# P07_PHY_2.net
KiCad netlist of a schematic drawn in Altium Designer
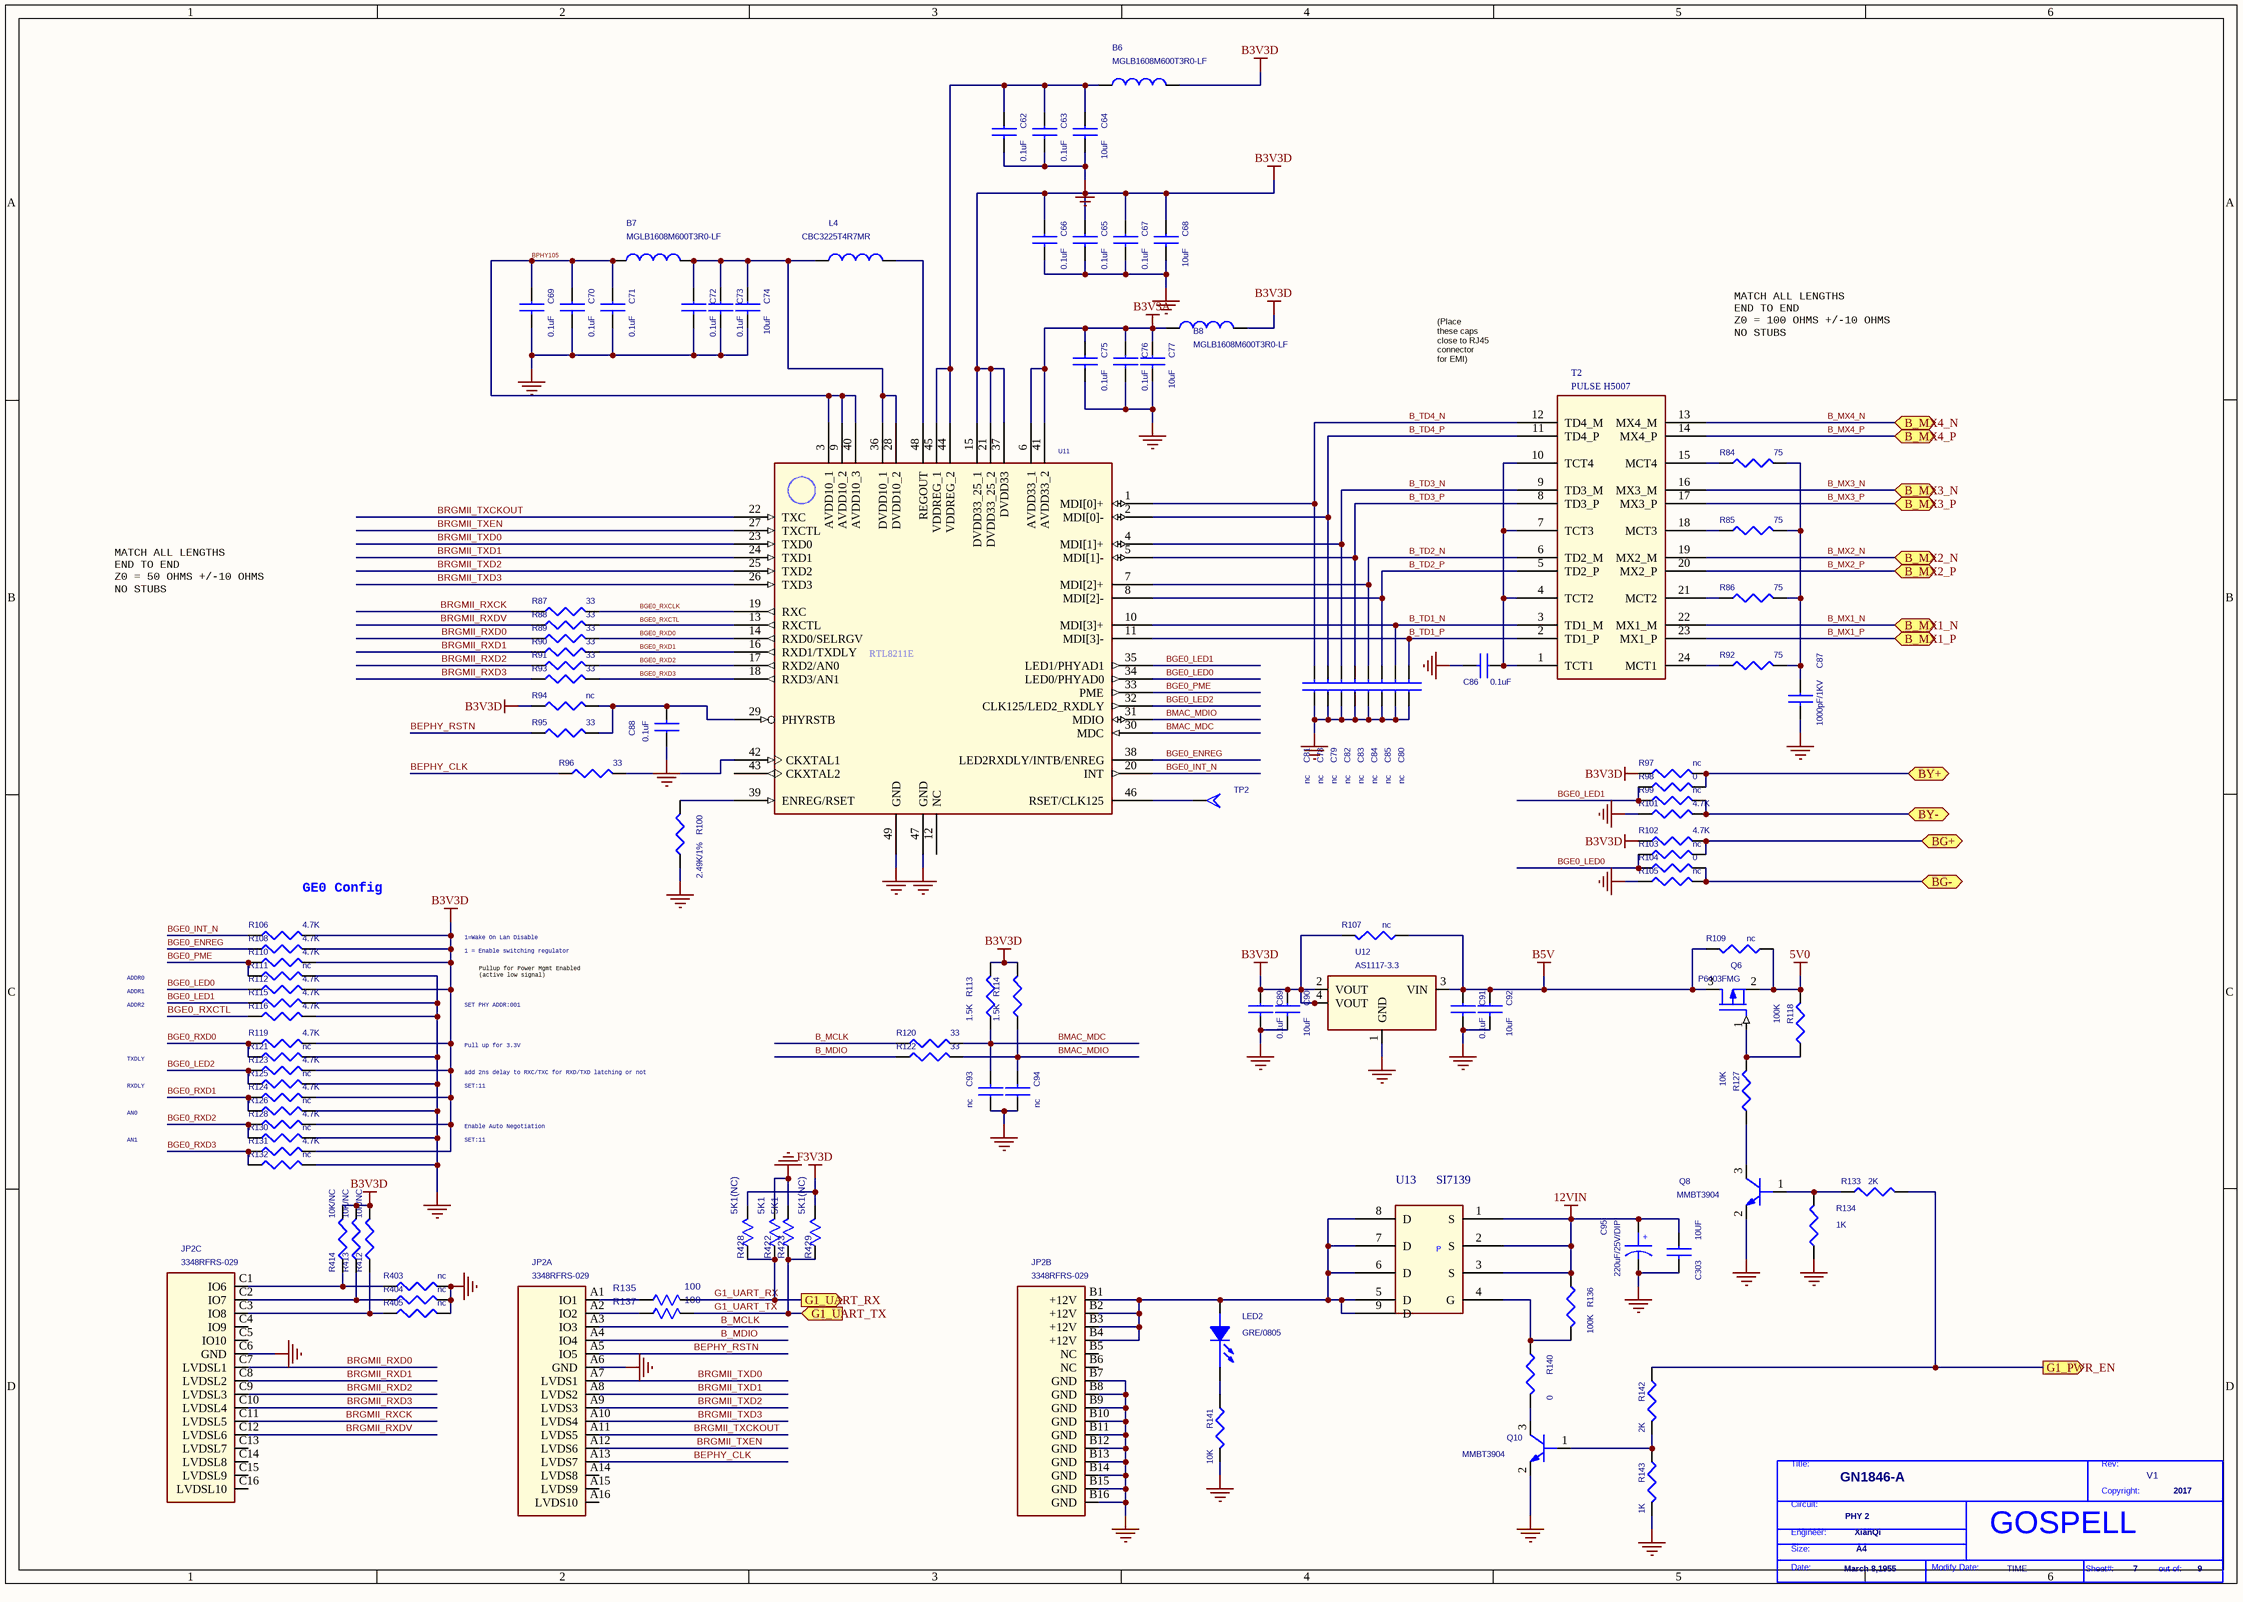
[diagram p0: P07 PHY 2.SchDoc]

(export (version "E")
  (design (tool "Eeschema 10.0.6"))
  (components
    (comp (ref "B6") (value "MGLB1608M600T3R0-LF") (libsource (lib "*") (part "CHOKE TORROID_0")))
    (comp (ref "B7") (value "MGLB1608M600T3R0-LF") (libsource (lib "*") (part "CHOKE TORROID_0")))
    (comp (ref "B8") (value "MGLB1608M600T3R0-LF") (libsource (lib "*") (part "CHOKE TORROID_0")))
    (comp (ref "C62") (value "0.1uF") (libsource (lib "*") (part "CAP NP_Dup1")))
    (comp (ref "C63") (value "0.1uF") (libsource (lib "*") (part "CAP NP_Dup1")))
    (comp (ref "C64") (value "10uF") (libsource (lib "*") (part "CAP NP_Dup1")))
    (comp (ref "C65") (value "0.1uF") (libsource (lib "*") (part "CAP NP_Dup1")))
    (comp (ref "C66") (value "0.1uF") (libsource (lib "*") (part "CAP NP_Dup1")))
    (comp (ref "C67") (value "0.1uF") (libsource (lib "*") (part "CAP NP_Dup1")))
    (comp (ref "C68") (value "10uF") (libsource (lib "*") (part "CAP NP_Dup1")))
    (comp (ref "C69") (value "0.1uF") (libsource (lib "*") (part "CAP NP_Dup1")))
    (comp (ref "C70") (value "0.1uF") (libsource (lib "*") (part "CAP NP_Dup1")))
    (comp (ref "C71") (value "0.1uF") (libsource (lib "*") (part "CAP NP_Dup1")))
    (comp (ref "C72") (value "0.1uF") (libsource (lib "*") (part "CAP NP_Dup1")))
    (comp (ref "C73") (value "0.1uF") (libsource (lib "*") (part "CAP NP_Dup1")))
    (comp (ref "C74") (value "10uF") (libsource (lib "*") (part "CAP NP_Dup1")))
    (comp (ref "C75") (value "0.1uF") (libsource (lib "*") (part "CAP NP_Dup1")))
    (comp (ref "C76") (value "0.1uF") (libsource (lib "*") (part "CAP NP_Dup1")))
    (comp (ref "C77") (value "10uF") (libsource (lib "*") (part "CAP NP_Dup1")))
    (comp (ref "C78") (value "nc") (libsource (lib "*") (part "CAP NP_Dup1")))
    (comp (ref "C79") (value "nc") (libsource (lib "*") (part "CAP NP_Dup1")))
    (comp (ref "C80") (value "nc") (libsource (lib "*") (part "CAP NP_Dup1")))
    (comp (ref "C81") (value "nc") (libsource (lib "*") (part "CAP NP_Dup1")))
    (comp (ref "C82") (value "nc") (libsource (lib "*") (part "CAP NP_Dup1")))
    (comp (ref "C83") (value "nc") (libsource (lib "*") (part "CAP NP_Dup1")))
    (comp (ref "C84") (value "nc") (libsource (lib "*") (part "CAP NP_Dup1")))
    (comp (ref "C85") (value "nc") (libsource (lib "*") (part "CAP NP_Dup1")))
    (comp (ref "C86") (value "0.1uF") (libsource (lib "*") (part "CAP NP_Dup1")))
    (comp (ref "C87") (value "1000pF/1KV") (libsource (lib "*") (part "CAP NP_Dup1")))
    (comp (ref "C88") (value "0.1uF") (libsource (lib "*") (part "CAP NP_Dup1")))
    (comp (ref "C89") (value "0.1uF") (libsource (lib "*") (part "CAP NP_Dup1")))
    (comp (ref "C90") (value "10uF") (libsource (lib "*") (part "CAP NP_Dup1")))
    (comp (ref "C91") (value "0.1uF") (libsource (lib "*") (part "CAP NP_Dup1")))
    (comp (ref "C92") (value "10uF") (libsource (lib "*") (part "CAP NP_Dup1")))
    (comp (ref "C93") (value "nc") (libsource (lib "*") (part "CAP NP_Dup1")))
    (comp (ref "C94") (value "nc") (libsource (lib "*") (part "CAP NP_Dup1")))
    (comp (ref "C95") (value "220uF/25V/DIP") (libsource (lib "*") (part "CAP POL")))
    (comp (ref "C303") (value "10UF") (libsource (lib "*") (part "CAP NP")))
    (comp (ref "JP2")
      (value "3348RFRS-029")
      (footprint "3348RFRS-029")
      (libsource (lib "*") (part "3348RFRS-029"))
    )
    (comp (ref "L4") (value "CBC3225T4R7MR") (libsource (lib "*") (part "CHOKE TORROID_0")))
    (comp (ref "LED2") (value "GRE/0805") (libsource (lib "*") (part "LED_0")))
    (comp (ref "Q6") (value "P6403FMG") (libsource (lib "*") (part "MOSFET P_0")))
    (comp (ref "Q8") (value "MMBT3904") (footprint "SOT23") (libsource (lib "*") (part "2N3904")))
    (comp (ref "Q10") (value "MMBT3904") (footprint "SOT23") (libsource (lib "*") (part "2N3904")))
    (comp (ref "R84") (value "75") (libsource (lib "*") (part "R_Dup1")))
    (comp (ref "R85") (value "75") (libsource (lib "*") (part "R_Dup1")))
    (comp (ref "R86") (value "75") (libsource (lib "*") (part "R_Dup1")))
    (comp (ref "R87") (value "33") (libsource (lib "*") (part "R_Dup1")))
    (comp (ref "R88") (value "33") (libsource (lib "*") (part "R_Dup1")))
    (comp (ref "R89") (value "33") (libsource (lib "*") (part "R_Dup1")))
    (comp (ref "R90") (value "33") (libsource (lib "*") (part "R_Dup1")))
    (comp (ref "R91") (value "33") (libsource (lib "*") (part "R_Dup1")))
    (comp (ref "R92") (value "75") (libsource (lib "*") (part "R_Dup1")))
    (comp (ref "R93") (value "33") (libsource (lib "*") (part "R_Dup1")))
    (comp (ref "R94") (value "nc") (libsource (lib "*") (part "R_Dup1")))
    (comp (ref "R95") (value "33") (libsource (lib "*") (part "R_Dup1")))
    (comp (ref "R96") (value "33") (libsource (lib "*") (part "R_Dup1")))
    (comp (ref "R97") (value "nc") (libsource (lib "*") (part "R_Dup1")))
    (comp (ref "R98") (value "0") (libsource (lib "*") (part "R_Dup1")))
    (comp (ref "R99") (value "nc") (libsource (lib "*") (part "R_Dup1")))
    (comp (ref "R100") (value "2.49K/1%") (libsource (lib "*") (part "R_Dup1")))
    (comp (ref "R101") (value "4.7K") (libsource (lib "*") (part "R_Dup1")))
    (comp (ref "R102") (value "4.7K") (libsource (lib "*") (part "R_Dup1")))
    (comp (ref "R103") (value "nc") (libsource (lib "*") (part "R_Dup1")))
    (comp (ref "R104") (value "0") (libsource (lib "*") (part "R_Dup1")))
    (comp (ref "R105") (value "nc") (libsource (lib "*") (part "R_Dup1")))
    (comp (ref "R106") (value "4.7K") (libsource (lib "*") (part "R_Dup1")))
    (comp (ref "R107") (value "nc") (libsource (lib "*") (part "R")))
    (comp (ref "R108") (value "4.7K") (libsource (lib "*") (part "R_Dup1")))
    (comp (ref "R109") (value "nc") (libsource (lib "*") (part "R")))
    (comp (ref "R110") (value "4.7K") (libsource (lib "*") (part "R_Dup1")))
    (comp (ref "R111") (value "nc") (libsource (lib "*") (part "R_Dup1")))
    (comp (ref "R112") (value "4.7K") (libsource (lib "*") (part "R_Dup1")))
    (comp (ref "R113") (value "1.5K") (libsource (lib "*") (part "R_Dup1")))
    (comp (ref "R114") (value "1.5K") (libsource (lib "*") (part "R_Dup1")))
    (comp (ref "R115") (value "4.7K") (libsource (lib "*") (part "R_Dup1")))
    (comp (ref "R116") (value "4.7K") (libsource (lib "*") (part "R_Dup1")))
    (comp (ref "R118") (value "100K") (libsource (lib "*") (part "R")))
    (comp (ref "R119") (value "4.7K") (libsource (lib "*") (part "R_Dup1")))
    (comp (ref "R120") (value "33") (libsource (lib "*") (part "R_Dup1")))
    (comp (ref "R121") (value "nc") (libsource (lib "*") (part "R_Dup1")))
    (comp (ref "R122") (value "33") (libsource (lib "*") (part "R_Dup1")))
    (comp (ref "R123") (value "4.7K") (libsource (lib "*") (part "R_Dup1")))
    (comp (ref "R124") (value "4.7K") (libsource (lib "*") (part "R_Dup1")))
    (comp (ref "R125") (value "nc") (libsource (lib "*") (part "R_Dup1")))
    (comp (ref "R126") (value "nc") (libsource (lib "*") (part "R_Dup1")))
    (comp (ref "R127") (value "10K") (libsource (lib "*") (part "R")))
    (comp (ref "R128") (value "4.7K") (libsource (lib "*") (part "R_Dup1")))
    (comp (ref "R130") (value "nc") (libsource (lib "*") (part "R_Dup1")))
    (comp (ref "R131") (value "4.7K") (libsource (lib "*") (part "R_Dup1")))
    (comp (ref "R132") (value "nc") (libsource (lib "*") (part "R_Dup1")))
    (comp (ref "R133") (value "2K") (libsource (lib "*") (part "R")))
    (comp (ref "R134") (value "1K") (libsource (lib "*") (part "R")))
    (comp (ref "R135") (value "100") (libsource (lib "*") (part "R_1")))
    (comp (ref "R136") (value "100K") (libsource (lib "*") (part "R_Dup1")))
    (comp (ref "R137") (value "100") (libsource (lib "*") (part "R_1")))
    (comp (ref "R140") (value "0") (libsource (lib "*") (part "R_Dup1")))
    (comp (ref "R141") (value "10K") (libsource (lib "*") (part "R_Dup1")))
    (comp (ref "R142") (value "2K") (libsource (lib "*") (part "R_Dup1")))
    (comp (ref "R143") (value "1K") (libsource (lib "*") (part "R_Dup1")))
    (comp (ref "R403") (value "nc") (libsource (lib "*") (part "R_Dup1")))
    (comp (ref "R404") (value "nc") (libsource (lib "*") (part "R_Dup1")))
    (comp (ref "R405") (value "nc") (libsource (lib "*") (part "R_Dup1")))
    (comp (ref "R412") (value "10K/NC") (libsource (lib "*") (part "R_Dup1")))
    (comp (ref "R413") (value "10K/NC") (libsource (lib "*") (part "R_Dup1")))
    (comp (ref "R414") (value "10K/NC") (libsource (lib "*") (part "R_Dup1")))
    (comp (ref "R422") (value "5K1") (libsource (lib "*") (part "R_1")))
    (comp (ref "R423") (value "5K1") (libsource (lib "*") (part "R_1")))
    (comp (ref "R428") (value "5K1(NC)") (libsource (lib "*") (part "R_1")))
    (comp (ref "R429") (value "5K1(NC)") (libsource (lib "*") (part "R_1")))
    (comp (ref "T2") (value "PULSE H5007") (footprint "H5007-H") (libsource (lib "*") (part "PULSE H5007_0")))
    (comp (ref "TP2") (value "T POINT A") (libsource (lib "*") (part "T POINT A")))
    (comp (ref "U11")
      (value "RTL8211D")
      (footprint "QFN-48P-RTL8211")
      (libsource (lib "*") (part "RTL8211D_1"))
    )
    (comp (ref "U12") (value "AS1117-3.3") (footprint "SOT223") (libsource (lib "*") (part "AS1117-X_1")))
    (comp (ref "U13")
      (value "SI7139")
      (footprint "PowerPAKSO8")
      (libsource (lib "GN-1846-A-V1_Library") (part "SI7139"))
    )
  )
  (nets
    (net (code "1") (name "/BEPHY_CLK") (class "Default")
      (node (ref "JP2") (pin "A13") (pinfunction "LVDS7_A13") (pintype "passive"))
      (node (ref "R96") (pin "1") (pinfunction "1_1") (pintype "passive"))
    )
    (net (code "2") (name "/BEPHY_RSTN") (class "Default")
      (node (ref "JP2") (pin "A5") (pinfunction "IO5_A5") (pintype "passive"))
      (node (ref "R95") (pin "1") (pinfunction "1_1") (pintype "passive"))
    )
    (net (code "3") (name "/BG+") (class "Default")
      (node (ref "R102") (pin "2") (pinfunction "2_2") (pintype "passive"))
      (node (ref "R103") (pin "2") (pinfunction "2_2") (pintype "passive"))
    )
    (net (code "4") (name "/BG-") (class "Default")
      (node (ref "R104") (pin "2") (pinfunction "2_2") (pintype "passive"))
      (node (ref "R105") (pin "2") (pinfunction "2_2") (pintype "passive"))
    )
    (net (code "5") (name "/BGE0_ENREG") (class "Default")
      (node (ref "R108") (pin "1") (pinfunction "1_1") (pintype "passive"))
      (node (ref "U11") (pin "38") (pinfunction "LED2RXDLY/INTB/ENREG_38") (pintype "passive"))
    )
    (net (code "6") (name "/BGE0_INT_N") (class "Default")
      (node (ref "R106") (pin "1") (pinfunction "1_1") (pintype "passive"))
      (node (ref "U11") (pin "20") (pinfunction "INT_20") (pintype "output"))
    )
    (net (code "7") (name "/BGE0_LED0") (class "Default")
      (node (ref "R103") (pin "1") (pinfunction "1_1") (pintype "passive"))
      (node (ref "R104") (pin "1") (pinfunction "1_1") (pintype "passive"))
      (node (ref "R112") (pin "1") (pinfunction "1_1") (pintype "passive"))
      (node (ref "U11") (pin "34") (pinfunction "LED0/PHYAD0_34") (pintype "output"))
    )
    (net (code "8") (name "/BGE0_LED1") (class "Default")
      (node (ref "R115") (pin "1") (pinfunction "1_1") (pintype "passive"))
      (node (ref "R98") (pin "1") (pinfunction "1_1") (pintype "passive"))
      (node (ref "R99") (pin "1") (pinfunction "1_1") (pintype "passive"))
      (node (ref "U11") (pin "35") (pinfunction "LED1/PHYAD1_35") (pintype "output"))
    )
    (net (code "9") (name "/BGE0_LED2") (class "Default")
      (node (ref "R123") (pin "1") (pinfunction "1_1") (pintype "passive"))
      (node (ref "R125") (pin "1") (pinfunction "1_1") (pintype "passive"))
      (node (ref "U11") (pin "32") (pinfunction "CLK125/LED2_RXDLY_32") (pintype "output"))
    )
    (net (code "10") (name "/BGE0_PME") (class "Default")
      (node (ref "R110") (pin "1") (pinfunction "1_1") (pintype "passive"))
      (node (ref "R111") (pin "1") (pinfunction "1_1") (pintype "passive"))
      (node (ref "U11") (pin "33") (pinfunction "PME_33") (pintype "output"))
    )
    (net (code "11") (name "/BGE0_RXCLK") (class "Default")
      (node (ref "R87") (pin "2") (pinfunction "2_2") (pintype "passive"))
      (node (ref "U11") (pin "19") (pinfunction "RXC_19") (pintype "output"))
    )
    (net (code "12") (name "/BGE0_RXCTL") (class "Default")
      (node (ref "R116") (pin "1") (pinfunction "1_1") (pintype "passive"))
      (node (ref "R88") (pin "2") (pinfunction "2_2") (pintype "passive"))
      (node (ref "U11") (pin "13") (pinfunction "RXCTL_13") (pintype "output"))
    )
    (net (code "13") (name "/BGE0_RXD0") (class "Default")
      (node (ref "R119") (pin "1") (pinfunction "1_1") (pintype "passive"))
      (node (ref "R121") (pin "1") (pinfunction "1_1") (pintype "passive"))
      (node (ref "R89") (pin "2") (pinfunction "2_2") (pintype "passive"))
      (node (ref "U11") (pin "14") (pinfunction "RXD0/SELRGV_14") (pintype "output"))
    )
    (net (code "14") (name "/BGE0_RXD1") (class "Default")
      (node (ref "R124") (pin "1") (pinfunction "1_1") (pintype "passive"))
      (node (ref "R126") (pin "1") (pinfunction "1_1") (pintype "passive"))
      (node (ref "R90") (pin "2") (pinfunction "2_2") (pintype "passive"))
      (node (ref "U11") (pin "16") (pinfunction "RXD1/TXDLY_16") (pintype "output"))
    )
    (net (code "15") (name "/BGE0_RXD2") (class "Default")
      (node (ref "R128") (pin "1") (pinfunction "1_1") (pintype "passive"))
      (node (ref "R130") (pin "1") (pinfunction "1_1") (pintype "passive"))
      (node (ref "R91") (pin "2") (pinfunction "2_2") (pintype "passive"))
      (node (ref "U11") (pin "17") (pinfunction "RXD2/AN0_17") (pintype "output"))
    )
    (net (code "16") (name "/BGE0_RXD3") (class "Default")
      (node (ref "R131") (pin "1") (pinfunction "1_1") (pintype "passive"))
      (node (ref "R132") (pin "1") (pinfunction "1_1") (pintype "passive"))
      (node (ref "R93") (pin "2") (pinfunction "2_2") (pintype "passive"))
      (node (ref "U11") (pin "18") (pinfunction "RXD3/AN1_18") (pintype "output"))
    )
    (net (code "17") (name "/BMAC_MDC") (class "Default")
      (node (ref "C93") (pin "2") (pinfunction "2_2") (pintype "passive"))
      (node (ref "R113") (pin "1") (pinfunction "1_1") (pintype "passive"))
      (node (ref "R120") (pin "2") (pinfunction "2_2") (pintype "passive"))
      (node (ref "U11") (pin "30") (pinfunction "MDC_30") (pintype "input"))
    )
    (net (code "18") (name "/BMAC_MDIO") (class "Default")
      (node (ref "C94") (pin "2") (pinfunction "2_2") (pintype "passive"))
      (node (ref "R114") (pin "1") (pinfunction "1_1") (pintype "passive"))
      (node (ref "R122") (pin "2") (pinfunction "2_2") (pintype "passive"))
      (node (ref "U11") (pin "31") (pinfunction "MDIO_31") (pintype "bidirectional"))
    )
    (net (code "19") (name "/BPHY105") (class "Default")
      (node (ref "B7") (pin "1") (pinfunction "1_1") (pintype "passive"))
      (node (ref "C69") (pin "1") (pinfunction "1_1") (pintype "passive"))
      (node (ref "C70") (pin "1") (pinfunction "1_1") (pintype "passive"))
      (node (ref "C71") (pin "1") (pinfunction "1_1") (pintype "passive"))
      (node (ref "U11") (pin "3") (pinfunction "AVDD10_1_3") (pintype "power_in"))
      (node (ref "U11") (pin "40") (pinfunction "AVDD10_3_40") (pintype "power_in"))
      (node (ref "U11") (pin "9") (pinfunction "AVDD10_2_9") (pintype "power_in"))
    )
    (net (code "20") (name "/BRGMII_RXCK") (class "Default")
      (node (ref "JP2") (pin "C11") (pinfunction "LVDSL5_C11") (pintype "passive"))
      (node (ref "R87") (pin "1") (pinfunction "1_1") (pintype "passive"))
    )
    (net (code "21") (name "/BRGMII_RXD0") (class "Default")
      (node (ref "JP2") (pin "C7") (pinfunction "LVDSL1_C7") (pintype "passive"))
      (node (ref "R89") (pin "1") (pinfunction "1_1") (pintype "passive"))
    )
    (net (code "22") (name "/BRGMII_RXD1") (class "Default")
      (node (ref "JP2") (pin "C8") (pinfunction "LVDSL2_C8") (pintype "passive"))
      (node (ref "R90") (pin "1") (pinfunction "1_1") (pintype "passive"))
    )
    (net (code "23") (name "/BRGMII_RXD2") (class "Default")
      (node (ref "JP2") (pin "C9") (pinfunction "LVDSL3_C9") (pintype "passive"))
      (node (ref "R91") (pin "1") (pinfunction "1_1") (pintype "passive"))
    )
    (net (code "24") (name "/BRGMII_RXD3") (class "Default")
      (node (ref "JP2") (pin "C10") (pinfunction "LVDSL4_C10") (pintype "passive"))
      (node (ref "R93") (pin "1") (pinfunction "1_1") (pintype "passive"))
    )
    (net (code "25") (name "/BRGMII_RXDV") (class "Default")
      (node (ref "JP2") (pin "C12") (pinfunction "LVDSL6_C12") (pintype "passive"))
      (node (ref "R88") (pin "1") (pinfunction "1_1") (pintype "passive"))
    )
    (net (code "26") (name "/BRGMII_TXCKOUT") (class "Default")
      (node (ref "JP2") (pin "A11") (pinfunction "LVDS5_A11") (pintype "passive"))
      (node (ref "U11") (pin "22") (pinfunction "TXC_22") (pintype "input"))
    )
    (net (code "27") (name "/BRGMII_TXD0") (class "Default")
      (node (ref "JP2") (pin "A7") (pinfunction "LVDS1_A7") (pintype "passive"))
      (node (ref "U11") (pin "23") (pinfunction "TXD0_23") (pintype "input"))
    )
    (net (code "28") (name "/BRGMII_TXD1") (class "Default")
      (node (ref "JP2") (pin "A8") (pinfunction "LVDS2_A8") (pintype "passive"))
      (node (ref "U11") (pin "24") (pinfunction "TXD1_24") (pintype "input"))
    )
    (net (code "29") (name "/BRGMII_TXD2") (class "Default")
      (node (ref "JP2") (pin "A9") (pinfunction "LVDS3_A9") (pintype "passive"))
      (node (ref "U11") (pin "25") (pinfunction "TXD2_25") (pintype "input"))
    )
    (net (code "30") (name "/BRGMII_TXD3") (class "Default")
      (node (ref "JP2") (pin "A10") (pinfunction "LVDS4_A10") (pintype "passive"))
      (node (ref "U11") (pin "26") (pinfunction "TXD3_26") (pintype "input"))
    )
    (net (code "31") (name "/BRGMII_TXEN") (class "Default")
      (node (ref "JP2") (pin "A12") (pinfunction "LVDS6_A12") (pintype "passive"))
      (node (ref "U11") (pin "27") (pinfunction "TXCTL_27") (pintype "input"))
    )
    (net (code "32") (name "/BY+") (class "Default")
      (node (ref "R97") (pin "2") (pinfunction "2_2") (pintype "passive"))
      (node (ref "R98") (pin "2") (pinfunction "2_2") (pintype "passive"))
    )
    (net (code "33") (name "/BY-") (class "Default")
      (node (ref "R101") (pin "2") (pinfunction "2_2") (pintype "passive"))
      (node (ref "R99") (pin "2") (pinfunction "2_2") (pintype "passive"))
    )
    (net (code "34") (name "/B_MCLK") (class "Default")
      (node (ref "JP2") (pin "A3") (pinfunction "IO3_A3") (pintype "passive"))
      (node (ref "R120") (pin "1") (pinfunction "1_1") (pintype "passive"))
    )
    (net (code "35") (name "/B_MDIO") (class "Default")
      (node (ref "JP2") (pin "A4") (pinfunction "IO4_A4") (pintype "passive"))
      (node (ref "R122") (pin "1") (pinfunction "1_1") (pintype "passive"))
    )
    (net (code "36") (name "/B_MX1_N") (class "Default")
      (node (ref "T2") (pin "22") (pinfunction "MX1_M_22") (pintype "passive"))
    )
    (net (code "37") (name "/B_MX1_P") (class "Default")
      (node (ref "T2") (pin "23") (pinfunction "MX1_P_23") (pintype "passive"))
    )
    (net (code "38") (name "/B_MX2_N") (class "Default")
      (node (ref "T2") (pin "19") (pinfunction "MX2_M_19") (pintype "passive"))
    )
    (net (code "39") (name "/B_MX2_P") (class "Default")
      (node (ref "T2") (pin "20") (pinfunction "MX2_P_20") (pintype "passive"))
    )
    (net (code "40") (name "/B_MX3_N") (class "Default")
      (node (ref "T2") (pin "16") (pinfunction "MX3_M_16") (pintype "passive"))
    )
    (net (code "41") (name "/B_MX3_P") (class "Default")
      (node (ref "T2") (pin "17") (pinfunction "MX3_P_17") (pintype "passive"))
    )
    (net (code "42") (name "/B_MX4_N") (class "Default")
      (node (ref "T2") (pin "13") (pinfunction "MX4_M_13") (pintype "passive"))
    )
    (net (code "43") (name "/B_MX4_P") (class "Default")
      (node (ref "T2") (pin "14") (pinfunction "MX4_P_14") (pintype "passive"))
    )
    (net (code "44") (name "/B_TD1_N") (class "Default")
      (node (ref "C85") (pin "2") (pinfunction "2_2") (pintype "passive"))
      (node (ref "T2") (pin "3") (pinfunction "TD1_M_3") (pintype "passive"))
      (node (ref "U11") (pin "10") (pinfunction "MDI[3]+_10") (pintype "passive"))
    )
    (net (code "45") (name "/B_TD1_P") (class "Default")
      (node (ref "C80") (pin "2") (pinfunction "2_2") (pintype "passive"))
      (node (ref "T2") (pin "2") (pinfunction "TD1_P_2") (pintype "passive"))
      (node (ref "U11") (pin "11") (pinfunction "MDI[3]-_11") (pintype "passive"))
    )
    (net (code "46") (name "/B_TD2_N") (class "Default")
      (node (ref "C83") (pin "2") (pinfunction "2_2") (pintype "passive"))
      (node (ref "T2") (pin "6") (pinfunction "TD2_M_6") (pintype "passive"))
      (node (ref "U11") (pin "7") (pinfunction "MDI[2]+_7") (pintype "passive"))
    )
    (net (code "47") (name "/B_TD2_P") (class "Default")
      (node (ref "C84") (pin "2") (pinfunction "2_2") (pintype "passive"))
      (node (ref "T2") (pin "5") (pinfunction "TD2_P_5") (pintype "passive"))
      (node (ref "U11") (pin "8") (pinfunction "MDI[2]-_8") (pintype "passive"))
    )
    (net (code "48") (name "/B_TD3_N") (class "Default")
      (node (ref "C79") (pin "2") (pinfunction "2_2") (pintype "passive"))
      (node (ref "T2") (pin "9") (pinfunction "TD3_M_9") (pintype "passive"))
      (node (ref "U11") (pin "4") (pinfunction "MDI[1]+_4") (pintype "bidirectional"))
    )
    (net (code "49") (name "/B_TD3_P") (class "Default")
      (node (ref "C82") (pin "2") (pinfunction "2_2") (pintype "passive"))
      (node (ref "T2") (pin "8") (pinfunction "TD3_P_8") (pintype "passive"))
      (node (ref "U11") (pin "5") (pinfunction "MDI[1]-_5") (pintype "bidirectional"))
    )
    (net (code "50") (name "/B_TD4_N") (class "Default")
      (node (ref "C81") (pin "2") (pinfunction "2_2") (pintype "passive"))
      (node (ref "T2") (pin "12") (pinfunction "TD4_M_12") (pintype "passive"))
      (node (ref "U11") (pin "1") (pinfunction "MDI[0]+_1") (pintype "bidirectional"))
    )
    (net (code "51") (name "/B_TD4_P") (class "Default")
      (node (ref "C78") (pin "2") (pinfunction "2_2") (pintype "passive"))
      (node (ref "T2") (pin "11") (pinfunction "TD4_P_11") (pintype "passive"))
      (node (ref "U11") (pin "2") (pinfunction "MDI[0]-_2") (pintype "bidirectional"))
    )
    (net (code "52") (name "/G1_PWR_EN") (class "Default")
      (node (ref "R133") (pin "2") (pinfunction "2_2") (pintype "passive"))
      (node (ref "R142") (pin "2") (pinfunction "2_2") (pintype "passive"))
    )
    (net (code "53") (name "/G1_UART_RX") (class "Default")
      (node (ref "R135") (pin "2") (pinfunction "B_2") (pintype "passive"))
      (node (ref "R422") (pin "1") (pinfunction "A_1") (pintype "passive"))
      (node (ref "R428") (pin "1") (pinfunction "A_1") (pintype "passive"))
    )
    (net (code "54") (name "/G1_UART_TX") (class "Default")
      (node (ref "R137") (pin "2") (pinfunction "B_2") (pintype "passive"))
      (node (ref "R423") (pin "1") (pinfunction "A_1") (pintype "passive"))
      (node (ref "R429") (pin "1") (pinfunction "A_1") (pintype "passive"))
    )
    (net (code "55") (name "5V0") (class "Default")
      (node (ref "Q6") (pin "2") (pinfunction "SOURCE_2") (pintype "passive"))
      (node (ref "R109") (pin "2") (pinfunction "2_2") (pintype "passive"))
      (node (ref "R118") (pin "1") (pinfunction "1_1") (pintype "passive"))
    )
    (net (code "56") (name "12VIN") (class "Default")
      (node (ref "C303") (pin "1") (pinfunction "1_1") (pintype "passive"))
      (node (ref "C95") (pin "1") (pinfunction "1_1") (pintype "passive"))
      (node (ref "R136") (pin "2") (pinfunction "2_2") (pintype "passive"))
      (node (ref "U13") (pin "1") (pinfunction "S_1") (pintype "passive"))
      (node (ref "U13") (pin "2") (pinfunction "S_2") (pintype "passive"))
      (node (ref "U13") (pin "3") (pinfunction "S_3") (pintype "passive"))
    )
    (net (code "57") (name "B3V3A") (class "Default")
      (node (ref "B8") (pin "1") (pinfunction "1_1") (pintype "passive"))
      (node (ref "C75") (pin "1") (pinfunction "1_1") (pintype "passive"))
      (node (ref "C76") (pin "1") (pinfunction "1_1") (pintype "passive"))
      (node (ref "C77") (pin "1") (pinfunction "1_1") (pintype "passive"))
      (node (ref "U11") (pin "41") (pinfunction "AVDD33_2_41") (pintype "power_in"))
      (node (ref "U11") (pin "6") (pinfunction "AVDD33_1_6") (pintype "power_in"))
    )
    (net (code "58") (name "B3V3D") (class "Default")
      (node (ref "B6") (pin "2") (pinfunction "2_2") (pintype "passive"))
      (node (ref "B8") (pin "2") (pinfunction "2_2") (pintype "passive"))
      (node (ref "C65") (pin "1") (pinfunction "1_1") (pintype "passive"))
      (node (ref "C66") (pin "1") (pinfunction "1_1") (pintype "passive"))
      (node (ref "C67") (pin "1") (pinfunction "1_1") (pintype "passive"))
      (node (ref "C68") (pin "1") (pinfunction "1_1") (pintype "passive"))
      (node (ref "C89") (pin "1") (pinfunction "1_1") (pintype "passive"))
      (node (ref "C90") (pin "1") (pinfunction "1_1") (pintype "passive"))
      (node (ref "R102") (pin "1") (pinfunction "1_1") (pintype "passive"))
      (node (ref "R106") (pin "2") (pinfunction "2_2") (pintype "passive"))
      (node (ref "R107") (pin "1") (pinfunction "1_1") (pintype "passive"))
      (node (ref "R108") (pin "2") (pinfunction "2_2") (pintype "passive"))
      (node (ref "R110") (pin "2") (pinfunction "2_2") (pintype "passive"))
      (node (ref "R112") (pin "2") (pinfunction "2_2") (pintype "passive"))
      (node (ref "R113") (pin "2") (pinfunction "2_2") (pintype "passive"))
      (node (ref "R114") (pin "2") (pinfunction "2_2") (pintype "passive"))
      (node (ref "R119") (pin "2") (pinfunction "2_2") (pintype "passive"))
      (node (ref "R123") (pin "2") (pinfunction "2_2") (pintype "passive"))
      (node (ref "R124") (pin "2") (pinfunction "2_2") (pintype "passive"))
      (node (ref "R128") (pin "2") (pinfunction "2_2") (pintype "passive"))
      (node (ref "R131") (pin "2") (pinfunction "2_2") (pintype "passive"))
      (node (ref "R412") (pin "2") (pinfunction "2_2") (pintype "passive"))
      (node (ref "R413") (pin "2") (pinfunction "2_2") (pintype "passive"))
      (node (ref "R414") (pin "2") (pinfunction "2_2") (pintype "passive"))
      (node (ref "R94") (pin "1") (pinfunction "1_1") (pintype "passive"))
      (node (ref "R97") (pin "1") (pinfunction "1_1") (pintype "passive"))
      (node (ref "U11") (pin "15") (pinfunction "DVDD33_25_1_15") (pintype "power_in"))
      (node (ref "U11") (pin "21") (pinfunction "DVDD33_25_2_21") (pintype "power_in"))
      (node (ref "U11") (pin "37") (pinfunction "DVDD33_37") (pintype "power_in"))
      (node (ref "U12") (pin "2") (pinfunction "VOUT_2") (pintype "passive"))
      (node (ref "U12") (pin "4") (pinfunction "VOUT_4") (pintype "passive"))
    )
    (net (code "59") (name "B5V") (class "Default")
      (node (ref "C91") (pin "1") (pinfunction "1_1") (pintype "passive"))
      (node (ref "C92") (pin "1") (pinfunction "1_1") (pintype "passive"))
      (node (ref "Q6") (pin "3") (pinfunction "DRAIN_3") (pintype "passive"))
      (node (ref "R107") (pin "2") (pinfunction "2_2") (pintype "passive"))
      (node (ref "R109") (pin "1") (pinfunction "1_1") (pintype "passive"))
      (node (ref "U12") (pin "3") (pinfunction "VIN_3") (pintype "passive"))
    )
    (net (code "60") (name "F3V3D") (class "Default")
      (node (ref "R428") (pin "2") (pinfunction "B_2") (pintype "passive"))
      (node (ref "R429") (pin "2") (pinfunction "B_2") (pintype "passive"))
    )
    (net (code "61") (name "GND") (class "Default")
      (node (ref "C303") (pin "2") (pinfunction "2_2") (pintype "passive"))
      (node (ref "C62") (pin "2") (pinfunction "2_2") (pintype "passive"))
      (node (ref "C63") (pin "2") (pinfunction "2_2") (pintype "passive"))
      (node (ref "C64") (pin "2") (pinfunction "2_2") (pintype "passive"))
      (node (ref "C65") (pin "2") (pinfunction "2_2") (pintype "passive"))
      (node (ref "C66") (pin "2") (pinfunction "2_2") (pintype "passive"))
      (node (ref "C67") (pin "2") (pinfunction "2_2") (pintype "passive"))
      (node (ref "C68") (pin "2") (pinfunction "2_2") (pintype "passive"))
      (node (ref "C69") (pin "2") (pinfunction "2_2") (pintype "passive"))
      (node (ref "C70") (pin "2") (pinfunction "2_2") (pintype "passive"))
      (node (ref "C71") (pin "2") (pinfunction "2_2") (pintype "passive"))
      (node (ref "C72") (pin "2") (pinfunction "2_2") (pintype "passive"))
      (node (ref "C73") (pin "2") (pinfunction "2_2") (pintype "passive"))
      (node (ref "C74") (pin "2") (pinfunction "2_2") (pintype "passive"))
      (node (ref "C75") (pin "2") (pinfunction "2_2") (pintype "passive"))
      (node (ref "C76") (pin "2") (pinfunction "2_2") (pintype "passive"))
      (node (ref "C77") (pin "2") (pinfunction "2_2") (pintype "passive"))
      (node (ref "C78") (pin "1") (pinfunction "1_1") (pintype "passive"))
      (node (ref "C79") (pin "1") (pinfunction "1_1") (pintype "passive"))
      (node (ref "C80") (pin "1") (pinfunction "1_1") (pintype "passive"))
      (node (ref "C81") (pin "1") (pinfunction "1_1") (pintype "passive"))
      (node (ref "C82") (pin "1") (pinfunction "1_1") (pintype "passive"))
      (node (ref "C83") (pin "1") (pinfunction "1_1") (pintype "passive"))
      (node (ref "C84") (pin "1") (pinfunction "1_1") (pintype "passive"))
      (node (ref "C85") (pin "1") (pinfunction "1_1") (pintype "passive"))
      (node (ref "C86") (pin "2") (pinfunction "2_2") (pintype "passive"))
      (node (ref "C87") (pin "2") (pinfunction "2_2") (pintype "passive"))
      (node (ref "C88") (pin "1") (pinfunction "1_1") (pintype "passive"))
      (node (ref "C89") (pin "2") (pinfunction "2_2") (pintype "passive"))
      (node (ref "C90") (pin "2") (pinfunction "2_2") (pintype "passive"))
      (node (ref "C91") (pin "2") (pinfunction "2_2") (pintype "passive"))
      (node (ref "C92") (pin "2") (pinfunction "2_2") (pintype "passive"))
      (node (ref "C93") (pin "1") (pinfunction "1_1") (pintype "passive"))
      (node (ref "C94") (pin "1") (pinfunction "1_1") (pintype "passive"))
      (node (ref "C95") (pin "2") (pinfunction "2_2") (pintype "passive"))
      (node (ref "JP2") (pin "A6") (pinfunction "GND_A6") (pintype "passive"))
      (node (ref "JP2") (pin "B10") (pinfunction "GND_B10") (pintype "passive"))
      (node (ref "JP2") (pin "B11") (pinfunction "GND_B11") (pintype "passive"))
      (node (ref "JP2") (pin "B12") (pinfunction "GND_B12") (pintype "passive"))
      (node (ref "JP2") (pin "B13") (pinfunction "GND_B13") (pintype "passive"))
      (node (ref "JP2") (pin "B14") (pinfunction "GND_B14") (pintype "passive"))
      (node (ref "JP2") (pin "B15") (pinfunction "GND_B15") (pintype "passive"))
      (node (ref "JP2") (pin "B16") (pinfunction "GND_B16") (pintype "passive"))
      (node (ref "JP2") (pin "B7") (pinfunction "GND_B7") (pintype "passive"))
      (node (ref "JP2") (pin "B8") (pinfunction "GND_B8") (pintype "passive"))
      (node (ref "JP2") (pin "B9") (pinfunction "GND_B9") (pintype "passive"))
      (node (ref "JP2") (pin "C6") (pinfunction "GND_C6") (pintype "passive"))
      (node (ref "Q10") (pin "2") (pinfunction "EMITTER_2") (pintype "passive"))
      (node (ref "Q8") (pin "2") (pinfunction "EMITTER_2") (pintype "passive"))
      (node (ref "R100") (pin "1") (pinfunction "1_1") (pintype "passive"))
      (node (ref "R101") (pin "1") (pinfunction "1_1") (pintype "passive"))
      (node (ref "R105") (pin "1") (pinfunction "1_1") (pintype "passive"))
      (node (ref "R111") (pin "2") (pinfunction "2_2") (pintype "passive"))
      (node (ref "R115") (pin "2") (pinfunction "2_2") (pintype "passive"))
      (node (ref "R116") (pin "2") (pinfunction "2_2") (pintype "passive"))
      (node (ref "R121") (pin "2") (pinfunction "2_2") (pintype "passive"))
      (node (ref "R125") (pin "2") (pinfunction "2_2") (pintype "passive"))
      (node (ref "R126") (pin "2") (pinfunction "2_2") (pintype "passive"))
      (node (ref "R130") (pin "2") (pinfunction "2_2") (pintype "passive"))
      (node (ref "R132") (pin "2") (pinfunction "2_2") (pintype "passive"))
      (node (ref "R134") (pin "1") (pinfunction "1_1") (pintype "passive"))
      (node (ref "R141") (pin "1") (pinfunction "1_1") (pintype "passive"))
      (node (ref "R143") (pin "1") (pinfunction "1_1") (pintype "passive"))
      (node (ref "R403") (pin "2") (pinfunction "2_2") (pintype "passive"))
      (node (ref "R404") (pin "2") (pinfunction "2_2") (pintype "passive"))
      (node (ref "R405") (pin "2") (pinfunction "2_2") (pintype "passive"))
      (node (ref "R422") (pin "2") (pinfunction "B_2") (pintype "passive"))
      (node (ref "R423") (pin "2") (pinfunction "B_2") (pintype "passive"))
      (node (ref "U11") (pin "47") (pinfunction "GND_47") (pintype "power_in"))
      (node (ref "U11") (pin "49") (pinfunction "GND_49") (pintype "power_in"))
      (node (ref "U12") (pin "1") (pinfunction "GND_1") (pintype "passive"))
    )
    (net (code "62") (name "Net-(C87-Pad1)") (class "Default")
      (node (ref "C87") (pin "1") (pinfunction "1_1") (pintype "passive"))
      (node (ref "R84") (pin "2") (pinfunction "2_2") (pintype "passive"))
      (node (ref "R85") (pin "2") (pinfunction "2_2") (pintype "passive"))
      (node (ref "R86") (pin "2") (pinfunction "2_2") (pintype "passive"))
      (node (ref "R92") (pin "2") (pinfunction "2_2") (pintype "passive"))
    )
    (net (code "63") (name "Net-(JP2A-IO1)") (class "Default")
      (node (ref "JP2") (pin "A1") (pinfunction "IO1_A1") (pintype "passive"))
      (node (ref "R135") (pin "1") (pinfunction "A_1") (pintype "passive"))
    )
    (net (code "64") (name "Net-(JP2A-IO2)") (class "Default")
      (node (ref "JP2") (pin "A2") (pinfunction "IO2_A2") (pintype "passive"))
      (node (ref "R137") (pin "1") (pinfunction "A_1") (pintype "passive"))
    )
    (net (code "65") (name "Net-(JP2C-IO6)") (class "Default")
      (node (ref "JP2") (pin "C1") (pinfunction "IO6_C1") (pintype "passive"))
      (node (ref "R403") (pin "1") (pinfunction "1_1") (pintype "passive"))
      (node (ref "R414") (pin "1") (pinfunction "1_1") (pintype "passive"))
    )
    (net (code "66") (name "Net-(JP2C-IO7)") (class "Default")
      (node (ref "JP2") (pin "C2") (pinfunction "IO7_C2") (pintype "passive"))
      (node (ref "R404") (pin "1") (pinfunction "1_1") (pintype "passive"))
      (node (ref "R413") (pin "1") (pinfunction "1_1") (pintype "passive"))
    )
    (net (code "67") (name "Net-(JP2C-IO8)") (class "Default")
      (node (ref "JP2") (pin "C3") (pinfunction "IO8_C3") (pintype "passive"))
      (node (ref "R405") (pin "1") (pinfunction "1_1") (pintype "passive"))
      (node (ref "R412") (pin "1") (pinfunction "1_1") (pintype "passive"))
    )
    (net (code "68") (name "Net-(LED2-ANODE)") (class "Default")
      (node (ref "JP2") (pin "B1") (pinfunction "+12V_B1") (pintype "passive"))
      (node (ref "JP2") (pin "B2") (pinfunction "+12V_B2") (pintype "passive"))
      (node (ref "JP2") (pin "B3") (pinfunction "+12V_B3") (pintype "passive"))
      (node (ref "JP2") (pin "B4") (pinfunction "+12V_B4") (pintype "passive"))
      (node (ref "LED2") (pin "A") (pinfunction "ANODE_A") (pintype "passive"))
      (node (ref "U13") (pin "5") (pinfunction "D_5") (pintype "passive"))
      (node (ref "U13") (pin "6") (pinfunction "D_6") (pintype "passive"))
      (node (ref "U13") (pin "7") (pinfunction "D_7") (pintype "passive"))
      (node (ref "U13") (pin "8") (pinfunction "D_8") (pintype "passive"))
      (node (ref "U13") (pin "9") (pinfunction "D_9") (pintype "passive"))
    )
    (net (code "69") (name "Net-(LED2-CATHODE)") (class "Default")
      (node (ref "LED2") (pin "K") (pinfunction "CATHODE_K") (pintype "passive"))
      (node (ref "R141") (pin "2") (pinfunction "2_2") (pintype "passive"))
    )
    (net (code "70") (name "Net-(Q6-GATE)") (class "Default")
      (node (ref "Q6") (pin "1") (pinfunction "GATE_1") (pintype "input"))
      (node (ref "R118") (pin "2") (pinfunction "2_2") (pintype "passive"))
      (node (ref "R127") (pin "1") (pinfunction "1_1") (pintype "passive"))
    )
    (net (code "71") (name "Net-(Q8-BASE)") (class "Default")
      (node (ref "Q8") (pin "1") (pinfunction "BASE_1") (pintype "passive"))
      (node (ref "R133") (pin "1") (pinfunction "1_1") (pintype "passive"))
      (node (ref "R134") (pin "2") (pinfunction "2_2") (pintype "passive"))
    )
    (net (code "72") (name "Net-(Q8-COLLECTOR)") (class "Default")
      (node (ref "Q8") (pin "3") (pinfunction "COLLECTOR_3") (pintype "passive"))
      (node (ref "R127") (pin "2") (pinfunction "2_2") (pintype "passive"))
    )
    (net (code "73") (name "Net-(Q10-BASE)") (class "Default")
      (node (ref "Q10") (pin "1") (pinfunction "BASE_1") (pintype "passive"))
      (node (ref "R142") (pin "1") (pinfunction "1_1") (pintype "passive"))
      (node (ref "R143") (pin "2") (pinfunction "2_2") (pintype "passive"))
    )
    (net (code "74") (name "Net-(Q10-COLLECTOR)") (class "Default")
      (node (ref "Q10") (pin "3") (pinfunction "COLLECTOR_3") (pintype "passive"))
      (node (ref "R140") (pin "1") (pinfunction "1_1") (pintype "passive"))
    )
    (net (code "75") (name "Net-(T2-MCT1)") (class "Default")
      (node (ref "R92") (pin "1") (pinfunction "1_1") (pintype "passive"))
      (node (ref "T2") (pin "24") (pinfunction "MCT1_24") (pintype "passive"))
    )
    (net (code "76") (name "Net-(T2-MCT2)") (class "Default")
      (node (ref "R86") (pin "1") (pinfunction "1_1") (pintype "passive"))
      (node (ref "T2") (pin "21") (pinfunction "MCT2_21") (pintype "passive"))
    )
    (net (code "77") (name "Net-(T2-MCT3)") (class "Default")
      (node (ref "R85") (pin "1") (pinfunction "1_1") (pintype "passive"))
      (node (ref "T2") (pin "18") (pinfunction "MCT3_18") (pintype "passive"))
    )
    (net (code "78") (name "Net-(T2-MCT4)") (class "Default")
      (node (ref "R84") (pin "1") (pinfunction "1_1") (pintype "passive"))
      (node (ref "T2") (pin "15") (pinfunction "MCT4_15") (pintype "passive"))
    )
    (net (code "79") (name "Net-(T2-TCT1)") (class "Default")
      (node (ref "C86") (pin "1") (pinfunction "1_1") (pintype "passive"))
      (node (ref "T2") (pin "1") (pinfunction "TCT1_1") (pintype "passive"))
      (node (ref "T2") (pin "10") (pinfunction "TCT4_10") (pintype "passive"))
      (node (ref "T2") (pin "4") (pinfunction "TCT2_4") (pintype "passive"))
      (node (ref "T2") (pin "7") (pinfunction "TCT3_7") (pintype "passive"))
    )
    (net (code "80") (name "Net-(TP2-TP)") (class "Default")
      (node (ref "TP2") (pin "1") (pinfunction "TP_1") (pintype "passive"))
      (node (ref "U11") (pin "46") (pinfunction "RSET/CLK125_46") (pintype "passive"))
    )
    (net (code "81") (name "Net-(U11-CKXTAL1)") (class "Default")
      (node (ref "R96") (pin "2") (pinfunction "2_2") (pintype "passive"))
      (node (ref "U11") (pin "42") (pinfunction "CKXTAL1_42") (pintype "input"))
    )
    (net (code "82") (name "Net-(U11-DVDD10_1)") (class "Default")
      (node (ref "B7") (pin "2") (pinfunction "2_2") (pintype "passive"))
      (node (ref "C72") (pin "1") (pinfunction "1_1") (pintype "passive"))
      (node (ref "C73") (pin "1") (pinfunction "1_1") (pintype "passive"))
      (node (ref "C74") (pin "1") (pinfunction "1_1") (pintype "passive"))
      (node (ref "L4") (pin "1") (pinfunction "1_1") (pintype "passive"))
      (node (ref "U11") (pin "28") (pinfunction "DVDD10_2_28") (pintype "power_in"))
      (node (ref "U11") (pin "36") (pinfunction "DVDD10_1_36") (pintype "power_in"))
    )
    (net (code "83") (name "Net-(U11-ENREG{slash}RSET)") (class "Default")
      (node (ref "R100") (pin "2") (pinfunction "2_2") (pintype "passive"))
      (node (ref "U11") (pin "39") (pinfunction "ENREG/RSET_39") (pintype "input"))
    )
    (net (code "84") (name "Net-(U11-PHYRSTB)") (class "Default")
      (node (ref "C88") (pin "2") (pinfunction "2_2") (pintype "passive"))
      (node (ref "R94") (pin "2") (pinfunction "2_2") (pintype "passive"))
      (node (ref "R95") (pin "2") (pinfunction "2_2") (pintype "passive"))
      (node (ref "U11") (pin "29") (pinfunction "PHYRSTB_29") (pintype "input"))
    )
    (net (code "85") (name "Net-(U11-REGOUT)") (class "Default")
      (node (ref "L4") (pin "2") (pinfunction "2_2") (pintype "passive"))
      (node (ref "U11") (pin "48") (pinfunction "REGOUT_48") (pintype "power_in"))
    )
    (net (code "86") (name "Net-(U11-VDDREG_1)") (class "Default")
      (node (ref "B6") (pin "1") (pinfunction "1_1") (pintype "passive"))
      (node (ref "C62") (pin "1") (pinfunction "1_1") (pintype "passive"))
      (node (ref "C63") (pin "1") (pinfunction "1_1") (pintype "passive"))
      (node (ref "C64") (pin "1") (pinfunction "1_1") (pintype "passive"))
      (node (ref "U11") (pin "44") (pinfunction "VDDREG_2_44") (pintype "power_in"))
      (node (ref "U11") (pin "45") (pinfunction "VDDREG_1_45") (pintype "power_in"))
    )
    (net (code "87") (name "Net-(U13-G)") (class "Default")
      (node (ref "R136") (pin "1") (pinfunction "1_1") (pintype "passive"))
      (node (ref "R140") (pin "2") (pinfunction "2_2") (pintype "passive"))
      (node (ref "U13") (pin "4") (pinfunction "G_4") (pintype "passive"))
    )
    (net (code "88") (name "unconnected-(JP2A-LVDS8-PadA14)") (class "Default")
      (node (ref "JP2") (pin "A14") (pinfunction "LVDS8_A14") (pintype "passive"))
    )
    (net (code "89") (name "unconnected-(JP2A-LVDS9-PadA15)") (class "Default")
      (node (ref "JP2") (pin "A15") (pinfunction "LVDS9_A15") (pintype "passive"))
    )
    (net (code "90") (name "unconnected-(JP2A-LVDS10-PadA16)") (class "Default")
      (node (ref "JP2") (pin "A16") (pinfunction "LVDS10_A16") (pintype "passive"))
    )
    (net (code "91") (name "unconnected-(JP2B-NC-PadB5)") (class "Default")
      (node (ref "JP2") (pin "B5") (pinfunction "NC_B5") (pintype "passive"))
    )
    (net (code "92") (name "unconnected-(JP2B-NC-PadB6)") (class "Default")
      (node (ref "JP2") (pin "B6") (pinfunction "NC_B6") (pintype "passive"))
    )
    (net (code "93") (name "unconnected-(JP2C-IO9-PadC4)") (class "Default")
      (node (ref "JP2") (pin "C4") (pinfunction "IO9_C4") (pintype "passive"))
    )
    (net (code "94") (name "unconnected-(JP2C-IO10-PadC5)") (class "Default")
      (node (ref "JP2") (pin "C5") (pinfunction "IO10_C5") (pintype "passive"))
    )
    (net (code "95") (name "unconnected-(JP2C-LVDSL7-PadC13)") (class "Default")
      (node (ref "JP2") (pin "C13") (pinfunction "LVDSL7_C13") (pintype "passive"))
    )
    (net (code "96") (name "unconnected-(JP2C-LVDSL8-PadC14)") (class "Default")
      (node (ref "JP2") (pin "C14") (pinfunction "LVDSL8_C14") (pintype "passive"))
    )
    (net (code "97") (name "unconnected-(JP2C-LVDSL9-PadC15)") (class "Default")
      (node (ref "JP2") (pin "C15") (pinfunction "LVDSL9_C15") (pintype "passive"))
    )
    (net (code "98") (name "unconnected-(JP2C-LVDSL10-PadC16)") (class "Default")
      (node (ref "JP2") (pin "C16") (pinfunction "LVDSL10_C16") (pintype "passive"))
    )
    (net (code "99") (name "unconnected-(U11-CKXTAL2-Pad43)") (class "Default")
      (node (ref "U11") (pin "43") (pinfunction "CKXTAL2_43") (pintype "output"))
    )
    (net (code "100") (name "unconnected-(U11-NC-Pad12)") (class "Default")
      (node (ref "U11") (pin "12") (pinfunction "NC_12") (pintype "passive"))
    )
  )
)
